# MIW_V3.net
KiCad netlist of a schematic drawn in EasyEDA Pro
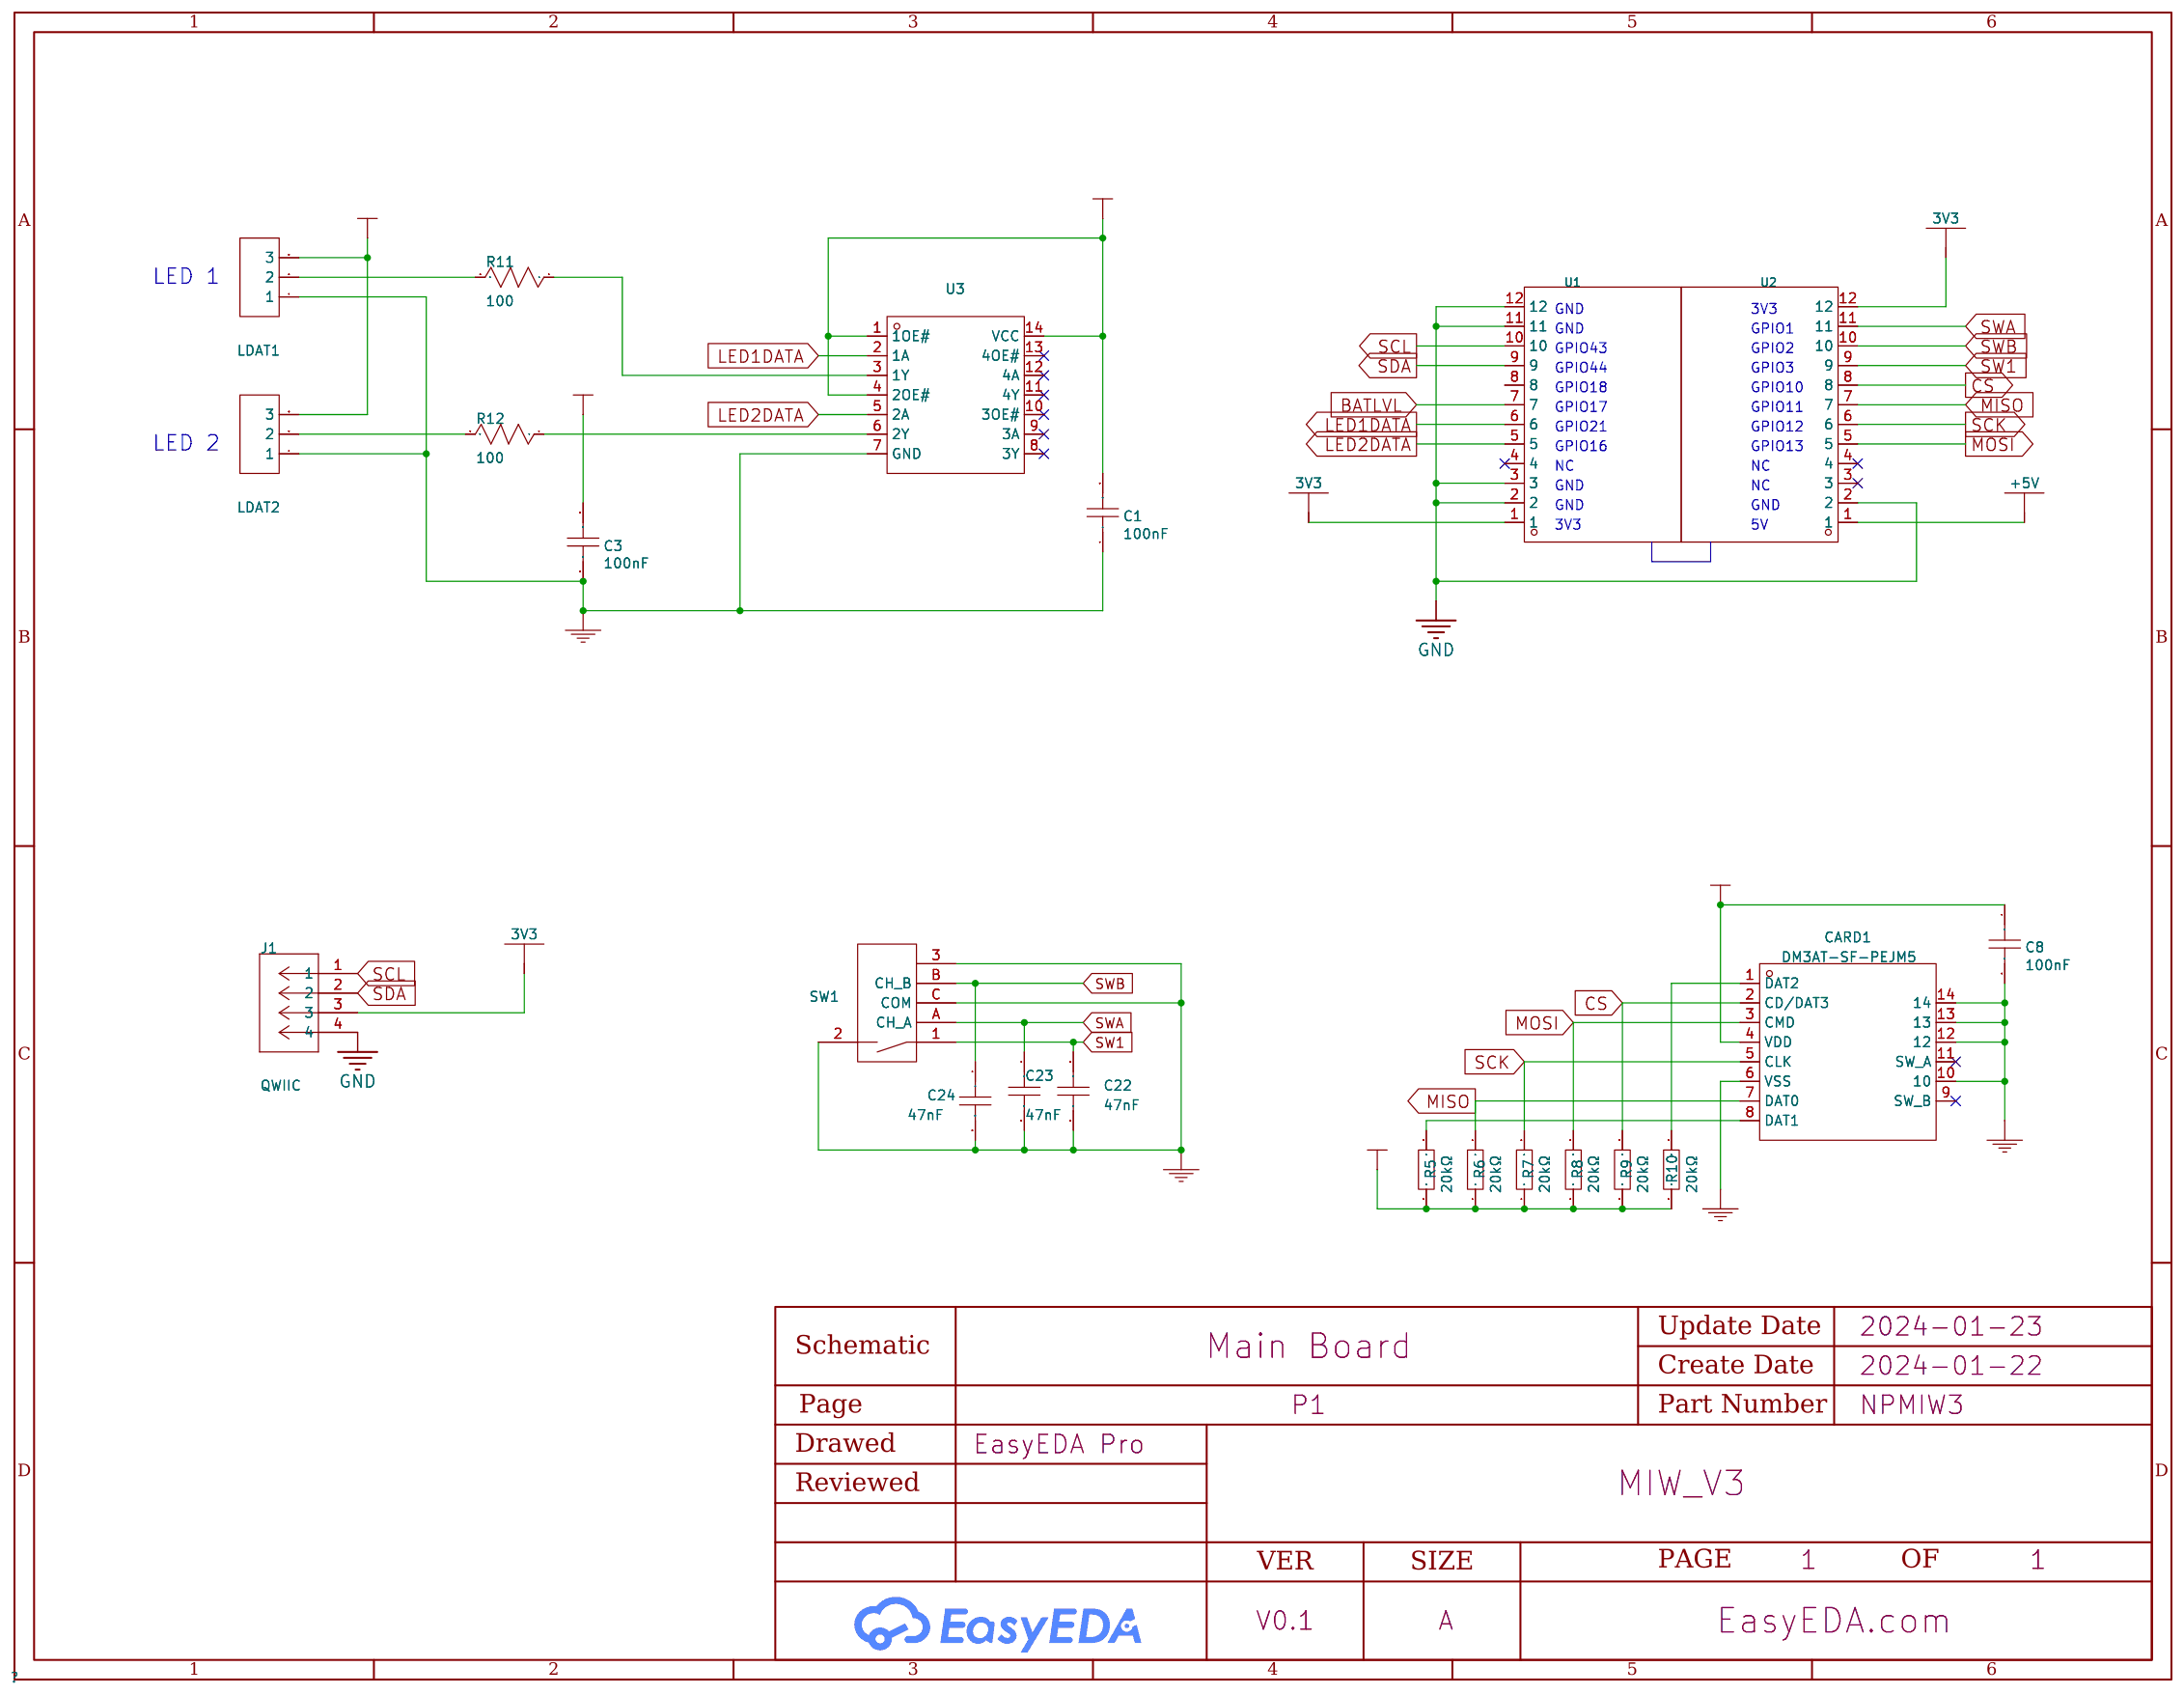
[diagram p0: schematic sheet]

(export (version "E")
  (design (tool "Eeschema 10.0.6"))
  (components
    (comp (ref "C1")
      (value "100nF")
      (footprint "easyedapro:C0603")
      (fields (field (name "Manufacturer Part") "CL10B104KC8NNNC") (field (name "Manufacturer") "SAMSUNG"))
      (libsource (lib "easyedapro") (part "100nF"))
    )
    (comp (ref "C3")
      (value "100nF")
      (footprint "easyedapro:C0603")
      (fields (field (name "Manufacturer Part") "CL10B104KC8NNNC") (field (name "Manufacturer") "SAMSUNG"))
      (libsource (lib "easyedapro") (part "100nF"))
    )
    (comp (ref "C8")
      (value "100nF")
      (fields
        (field (name "Manufacturer Part") "CL10B104KC8NNNC")
        (field (name "Manufacturer") "SAMSUNG(三星)")
      )
      (libsource (lib "easyedapro") (part "100nf"))
    )
    (comp (ref "C22")
      (value "47nF")
      (fields (field (name "Manufacturer Part") "CGA2B2X5R1E473K050BA") (field (name "Manufacturer") "TDK"))
      (libsource (lib "easyedapro") (part "cap"))
    )
    (comp (ref "C23")
      (value "47nF")
      (fields (field (name "Manufacturer Part") "CGA2B2X5R1E473K050BA") (field (name "Manufacturer") "TDK"))
      (libsource (lib "easyedapro") (part "cap"))
    )
    (comp (ref "C24")
      (value "47nF")
      (fields (field (name "Manufacturer Part") "CGA2B2X5R1E473K050BA") (field (name "Manufacturer") "TDK"))
      (libsource (lib "easyedapro") (part "cap"))
    )
    (comp (ref "CARD1")
      (value "DM3AT-SF-PEJM5")
      (fields (field (name "Manufacturer") "HRS(广濑)"))
      (libsource (lib "easyedapro") (part "dm3at-sf-pejm5"))
    )
    (comp (ref "J1")
      (value "PRT-16766")
      (footprint "easyedapro:CONN_BM04B-SRSS-TB_SPK")
      (fields (field (name "Manufacturer") "SparkFun"))
      (libsource (lib "easyedapro") (part "PRT-16766"))
    )
    (comp (ref "LDAT1")
      (value "HDR-M-2.54_1x3")
      (footprint "easyedapro:HDR-M-2.54_1X3")
      (libsource (lib "easyedapro") (part "HDR-M-2.54_1x3"))
    )
    (comp (ref "LDAT2")
      (value "HDR-M-2.54_1x3")
      (footprint "easyedapro:HDR-M-2.54_1X3")
      (libsource (lib "easyedapro") (part "HDR-M-2.54_1x3"))
    )
    (comp (ref "R5")
      (value "20kΩ")
      (fields (field (name "Manufacturer Part") "RC0402FR-0720KL") (field (name "Manufacturer") "YAGEO(国巨)"))
      (libsource (lib "easyedapro") (part "20kω"))
    )
    (comp (ref "R6")
      (value "20kΩ")
      (fields (field (name "Manufacturer Part") "RC0402FR-0720KL") (field (name "Manufacturer") "YAGEO(国巨)"))
      (libsource (lib "easyedapro") (part "20kω"))
    )
    (comp (ref "R7")
      (value "20kΩ")
      (fields (field (name "Manufacturer Part") "RC0402FR-0720KL") (field (name "Manufacturer") "YAGEO(国巨)"))
      (libsource (lib "easyedapro") (part "20kω"))
    )
    (comp (ref "R8")
      (value "20kΩ")
      (fields (field (name "Manufacturer Part") "RC0402FR-0720KL") (field (name "Manufacturer") "YAGEO(国巨)"))
      (libsource (lib "easyedapro") (part "20kω"))
    )
    (comp (ref "R9")
      (value "20kΩ")
      (fields (field (name "Manufacturer Part") "RC0402FR-0720KL") (field (name "Manufacturer") "YAGEO(国巨)"))
      (libsource (lib "easyedapro") (part "20kω"))
    )
    (comp (ref "R10")
      (value "20kΩ")
      (fields (field (name "Manufacturer Part") "RC0402FR-0720KL") (field (name "Manufacturer") "YAGEO(国巨)"))
      (libsource (lib "easyedapro") (part "20kω"))
    )
    (comp (ref "R11")
      (value "100")
      (footprint "easyedapro:R0603")
      (fields (field (name "Manufacturer Part") "0603WAF1000T5E") (field (name "Manufacturer") "UniOhm"))
      (libsource (lib "easyedapro") (part "100"))
    )
    (comp (ref "R12")
      (value "100")
      (footprint "easyedapro:R0603")
      (fields (field (name "Manufacturer Part") "0603WAF1000T5E") (field (name "Manufacturer") "UniOhm"))
      (libsource (lib "easyedapro") (part "100"))
    )
    (comp (ref "SW1")
      (value "PEC11R-4220F-S0012")
      (fields (field (name "Manufacturer") "BOURNS"))
      (libsource (lib "easyedapro") (part "pec11r-4220f-s0012"))
    )
    (comp (ref "U1")
      (value "ZX-PM2.54-1-12PY")
      (footprint "easyedapro:HDR-TH_12P-P2.54-V-F")
      (fields (field (name "Manufacturer") "Megastar(兆星)"))
      (libsource (lib "easyedapro") (part "ZX-PM2.54-1-12PY"))
    )
    (comp (ref "U2")
      (value "ZX-PM2.54-1-12PY")
      (footprint "easyedapro:HDR-TH_12P-P2.54-V-F")
      (fields (field (name "Manufacturer") "Megastar(兆星)"))
      (libsource (lib "easyedapro") (part "ZX-PM2.54-1-12PY"))
    )
    (comp (ref "U3")
      (value "74VHCT126AFT")
      (footprint "easyedapro:TSSOP-14_L5.0-W4.4-P0.65-LS6.4-BL")
      (fields (field (name "Manufacturer") "TOSHIBA(东芝)"))
      (libsource (lib "easyedapro") (part "74HCT125PW-Q100J"))
    )
  )
  (nets
    (net (code "1") (name "+5V") (class "Default")
      (node (ref "C1") (pin "2") (pinfunction "2_2") (pintype "unspecified"))
      (node (ref "C3") (pin "2") (pinfunction "2_2") (pintype "unspecified"))
      (node (ref "LDAT1") (pin "3") (pinfunction "3_3") (pintype "input"))
      (node (ref "LDAT2") (pin "3") (pinfunction "3_3") (pintype "input"))
      (node (ref "U2") (pin "1") (pinfunction "1_1") (pintype "input"))
      (node (ref "U3") (pin "1") (pinfunction "1OE#_1") (pintype "unspecified"))
      (node (ref "U3") (pin "14") (pinfunction "VCC_14") (pintype "unspecified"))
      (node (ref "U3") (pin "4") (pinfunction "2OE#_4") (pintype "unspecified"))
    )
    (net (code "2") (name "3V3") (class "Default")
      (node (ref "C8") (pin "1") (pinfunction "1_1") (pintype "unspecified"))
      (node (ref "CARD1") (pin "4") (pinfunction "VDD_4") (pintype "unspecified"))
      (node (ref "J1") (pin "3") (pinfunction "3_3") (pintype "unspecified"))
      (node (ref "R10") (pin "1") (pinfunction "1_1") (pintype "input"))
      (node (ref "R5") (pin "1") (pinfunction "1_1") (pintype "input"))
      (node (ref "R6") (pin "1") (pinfunction "1_1") (pintype "input"))
      (node (ref "R7") (pin "1") (pinfunction "1_1") (pintype "input"))
      (node (ref "R8") (pin "1") (pinfunction "1_1") (pintype "input"))
      (node (ref "R9") (pin "1") (pinfunction "1_1") (pintype "input"))
      (node (ref "U1") (pin "1") (pinfunction "1_1") (pintype "input"))
      (node (ref "U2") (pin "12") (pinfunction "12_12") (pintype "input"))
    )
    (net (code "3") (name "BATLVL") (class "Default")
      (node (ref "U1") (pin "7") (pinfunction "7_7") (pintype "input"))
    )
    (net (code "4") (name "CS") (class "Default")
      (node (ref "CARD1") (pin "2") (pinfunction "CD/DAT3_2") (pintype "unspecified"))
      (node (ref "R9") (pin "2") (pinfunction "2_2") (pintype "input"))
      (node (ref "U2") (pin "8") (pinfunction "8_8") (pintype "input"))
    )
    (net (code "5") (name "GND") (class "Default")
      (node (ref "C1") (pin "1") (pinfunction "1_1") (pintype "unspecified"))
      (node (ref "C22") (pin "2") (pinfunction "2_2") (pintype "input"))
      (node (ref "C23") (pin "2") (pinfunction "2_2") (pintype "input"))
      (node (ref "C24") (pin "2") (pinfunction "2_2") (pintype "input"))
      (node (ref "C3") (pin "1") (pinfunction "1_1") (pintype "unspecified"))
      (node (ref "C8") (pin "2") (pinfunction "2_2") (pintype "unspecified"))
      (node (ref "CARD1") (pin "10") (pinfunction "10_10") (pintype "unspecified"))
      (node (ref "CARD1") (pin "12") (pinfunction "12_12") (pintype "unspecified"))
      (node (ref "CARD1") (pin "13") (pinfunction "13_13") (pintype "unspecified"))
      (node (ref "CARD1") (pin "14") (pinfunction "14_14") (pintype "unspecified"))
      (node (ref "CARD1") (pin "6") (pinfunction "VSS_6") (pintype "unspecified"))
      (node (ref "J1") (pin "4") (pinfunction "4_4") (pintype "unspecified"))
      (node (ref "LDAT1") (pin "1") (pinfunction "1_1") (pintype "input"))
      (node (ref "LDAT2") (pin "1") (pinfunction "1_1") (pintype "input"))
      (node (ref "SW1") (pin "2") (pintype "bidirectional"))
      (node (ref "SW1") (pin "3") (pintype "unspecified"))
      (node (ref "SW1") (pin "C") (pinfunction "COM_C") (pintype "input"))
      (node (ref "U1") (pin "11") (pinfunction "11_11") (pintype "input"))
      (node (ref "U1") (pin "12") (pinfunction "12_12") (pintype "input"))
      (node (ref "U1") (pin "2") (pinfunction "2_2") (pintype "input"))
      (node (ref "U1") (pin "3") (pinfunction "3_3") (pintype "input"))
      (node (ref "U2") (pin "2") (pinfunction "2_2") (pintype "input"))
      (node (ref "U3") (pin "7") (pinfunction "GND_7") (pintype "unspecified"))
    )
    (net (code "6") (name "LED1DATA") (class "Default")
      (node (ref "U1") (pin "6") (pinfunction "6_6") (pintype "input"))
      (node (ref "U3") (pin "2") (pinfunction "1A_2") (pintype "unspecified"))
    )
    (net (code "7") (name "LED2DATA") (class "Default")
      (node (ref "U1") (pin "5") (pinfunction "5_5") (pintype "input"))
      (node (ref "U3") (pin "5") (pinfunction "2A_5") (pintype "unspecified"))
    )
    (net (code "8") (name "MISO") (class "Default")
      (node (ref "CARD1") (pin "7") (pinfunction "DAT0_7") (pintype "unspecified"))
      (node (ref "R6") (pin "2") (pinfunction "2_2") (pintype "input"))
      (node (ref "U2") (pin "7") (pinfunction "7_7") (pintype "input"))
    )
    (net (code "9") (name "MOSI") (class "Default")
      (node (ref "CARD1") (pin "3") (pinfunction "CMD_3") (pintype "unspecified"))
      (node (ref "R8") (pin "2") (pinfunction "2_2") (pintype "input"))
      (node (ref "U2") (pin "5") (pinfunction "5_5") (pintype "input"))
    )
    (net (code "10") (name "Net-(CARD1-DAT1)") (class "Default")
      (node (ref "CARD1") (pin "8") (pinfunction "DAT1_8") (pintype "unspecified"))
      (node (ref "R5") (pin "2") (pinfunction "2_2") (pintype "input"))
    )
    (net (code "11") (name "Net-(CARD1-DAT2)") (class "Default")
      (node (ref "CARD1") (pin "1") (pinfunction "DAT2_1") (pintype "unspecified"))
      (node (ref "R10") (pin "2") (pinfunction "2_2") (pintype "input"))
    )
    (net (code "12") (name "Net-(LDAT1-Pad2)") (class "Default")
      (node (ref "LDAT1") (pin "2") (pinfunction "2_2") (pintype "input"))
      (node (ref "R11") (pin "2") (pinfunction "2_2") (pintype "unspecified"))
    )
    (net (code "13") (name "Net-(LDAT2-Pad2)") (class "Default")
      (node (ref "LDAT2") (pin "2") (pinfunction "2_2") (pintype "input"))
      (node (ref "R12") (pin "2") (pinfunction "2_2") (pintype "unspecified"))
    )
    (net (code "14") (name "Net-(U3-1Y)") (class "Default")
      (node (ref "R11") (pin "1") (pinfunction "1_1") (pintype "unspecified"))
      (node (ref "U3") (pin "3") (pinfunction "1Y_3") (pintype "unspecified"))
    )
    (net (code "15") (name "Net-(U3-2Y)") (class "Default")
      (node (ref "R12") (pin "1") (pinfunction "1_1") (pintype "unspecified"))
      (node (ref "U3") (pin "6") (pinfunction "2Y_6") (pintype "unspecified"))
    )
    (net (code "16") (name "SCK") (class "Default")
      (node (ref "CARD1") (pin "5") (pinfunction "CLK_5") (pintype "unspecified"))
      (node (ref "R7") (pin "2") (pinfunction "2_2") (pintype "input"))
      (node (ref "U2") (pin "6") (pinfunction "6_6") (pintype "input"))
    )
    (net (code "17") (name "SCL") (class "Default")
      (node (ref "J1") (pin "1") (pinfunction "1_1") (pintype "unspecified"))
      (node (ref "U1") (pin "10") (pinfunction "10_10") (pintype "input"))
    )
    (net (code "18") (name "SDA") (class "Default")
      (node (ref "J1") (pin "2") (pinfunction "2_2") (pintype "unspecified"))
      (node (ref "U1") (pin "9") (pinfunction "9_9") (pintype "input"))
    )
    (net (code "19") (name "SW1") (class "Default")
      (node (ref "C22") (pin "1") (pinfunction "1_1") (pintype "input"))
      (node (ref "SW1") (pin "1") (pintype "bidirectional"))
      (node (ref "U2") (pin "9") (pinfunction "9_9") (pintype "input"))
    )
    (net (code "20") (name "SWA") (class "Default")
      (node (ref "C23") (pin "1") (pinfunction "1_1") (pintype "input"))
      (node (ref "SW1") (pin "A") (pinfunction "CH_A_A") (pintype "bidirectional"))
      (node (ref "U2") (pin "11") (pinfunction "11_11") (pintype "input"))
    )
    (net (code "21") (name "SWB") (class "Default")
      (node (ref "C24") (pin "1") (pinfunction "1_1") (pintype "input"))
      (node (ref "SW1") (pin "B") (pinfunction "CH_B_B") (pintype "bidirectional"))
      (node (ref "U2") (pin "10") (pinfunction "10_10") (pintype "input"))
    )
    (net (code "22") (name "unconnected-(CARD1-SW_A-Pad11)") (class "Default")
      (node (ref "CARD1") (pin "11") (pinfunction "SW_A_11") (pintype "unspecified+no_connect"))
    )
    (net (code "23") (name "unconnected-(CARD1-SW_B-Pad9)") (class "Default")
      (node (ref "CARD1") (pin "9") (pinfunction "SW_B_9") (pintype "unspecified+no_connect"))
    )
    (net (code "24") (name "unconnected-(U1-Pad4)") (class "Default")
      (node (ref "U1") (pin "4") (pinfunction "4_4") (pintype "input+no_connect"))
    )
    (net (code "25") (name "unconnected-(U1-Pad8)") (class "Default")
      (node (ref "U1") (pin "8") (pinfunction "8_8") (pintype "input"))
    )
    (net (code "26") (name "unconnected-(U2-Pad3)") (class "Default")
      (node (ref "U2") (pin "3") (pinfunction "3_3") (pintype "input+no_connect"))
    )
    (net (code "27") (name "unconnected-(U2-Pad4)") (class "Default")
      (node (ref "U2") (pin "4") (pinfunction "4_4") (pintype "input+no_connect"))
    )
    (net (code "28") (name "unconnected-(U3-3A-Pad9)") (class "Default")
      (node (ref "U3") (pin "9") (pinfunction "3A_9") (pintype "unspecified+no_connect"))
    )
    (net (code "29") (name "unconnected-(U3-3OE#-Pad10)") (class "Default")
      (node (ref "U3") (pin "10") (pinfunction "3OE#_10") (pintype "unspecified+no_connect"))
    )
    (net (code "30") (name "unconnected-(U3-3Y-Pad8)") (class "Default")
      (node (ref "U3") (pin "8") (pinfunction "3Y_8") (pintype "unspecified+no_connect"))
    )
    (net (code "31") (name "unconnected-(U3-4A-Pad12)") (class "Default")
      (node (ref "U3") (pin "12") (pinfunction "4A_12") (pintype "unspecified+no_connect"))
    )
    (net (code "32") (name "unconnected-(U3-4OE#-Pad13)") (class "Default")
      (node (ref "U3") (pin "13") (pinfunction "4OE#_13") (pintype "unspecified+no_connect"))
    )
    (net (code "33") (name "unconnected-(U3-4Y-Pad11)") (class "Default")
      (node (ref "U3") (pin "11") (pinfunction "4Y_11") (pintype "unspecified+no_connect"))
    )
  )
)
